# KONMAI_Cardreader.net
KiCad netlist of a schematic drawn in Altium Designer
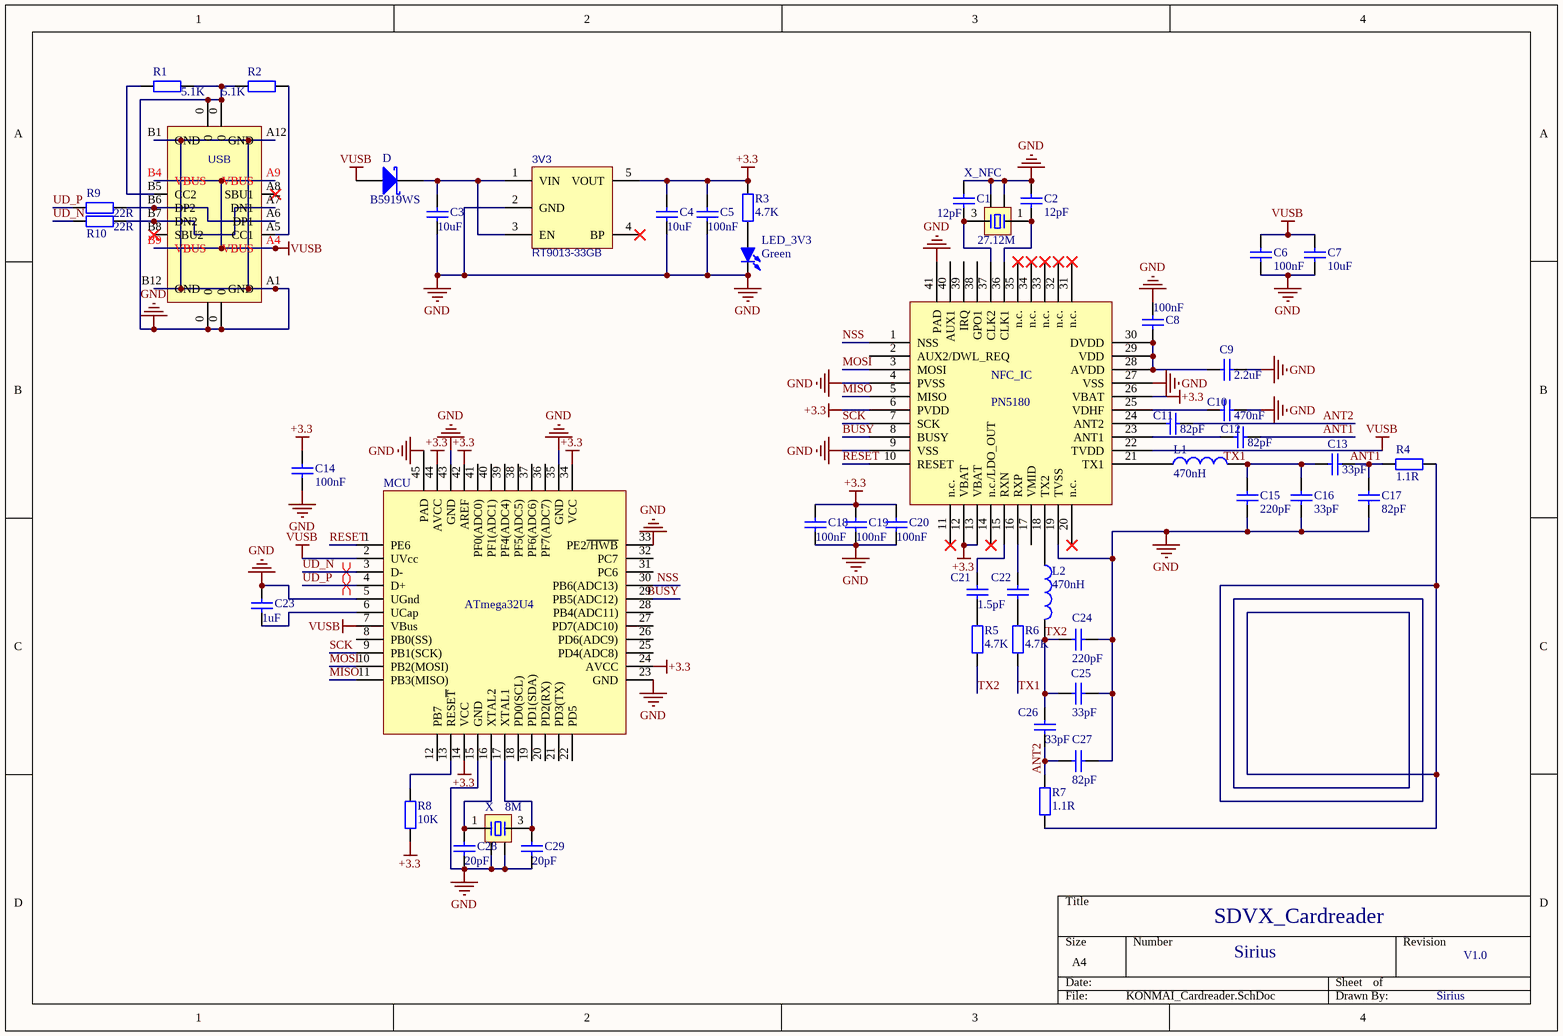
[diagram p0: KONMAI_Cardreader.SchDoc]

(export (version "E")
  (design (tool "Eeschema 10.0.6"))
  (components
    (comp (ref "3V3")
      (value "RT9013-33GB")
      (footprint "SOT-23-5")
      (description "LDO 3.0V/0.3A")
      (libsource (lib "0.7 - 电源类芯片") (part "RT9193-30GB"))
    )
    (comp (ref "C1")
      (value "12pF")
      (footprint "C0603_L")
      (description "贴片电容")
      (libsource (lib "0.1 - 电阻-电容-电感-电位器") (part "C"))
    )
    (comp (ref "C2")
      (value "12pF")
      (footprint "C0603_L")
      (description "贴片电容")
      (libsource (lib "0.1 - 电阻-电容-电感-电位器") (part "C"))
    )
    (comp (ref "C3")
      (value "10uF")
      (footprint "C0603_L")
      (description "贴片电容")
      (libsource (lib "0.1 - 电阻-电容-电感-电位器") (part "C"))
    )
    (comp (ref "C4")
      (value "10uF")
      (footprint "C0603_L")
      (description "贴片电容")
      (libsource (lib "0.1 - 电阻-电容-电感-电位器") (part "C"))
    )
    (comp (ref "C5")
      (value "100nF")
      (footprint "C0603_L")
      (description "贴片电容")
      (libsource (lib "0.1 - 电阻-电容-电感-电位器") (part "C"))
    )
    (comp (ref "C6")
      (value "100nF")
      (footprint "C0603_L")
      (description "TVDD续流电容")
      (libsource (lib "0.1 - 电阻-电容-电感-电位器") (part "C"))
    )
    (comp (ref "C7")
      (value "10uF")
      (footprint "C0603_L")
      (description "TVDD续流电容")
      (libsource (lib "0.1 - 电阻-电容-电感-电位器") (part "C"))
    )
    (comp (ref "C8")
      (value "100nF")
      (footprint "C0603_L")
      (description "DVDD滤波")
      (libsource (lib "0.1 - 电阻-电容-电感-电位器") (part "C"))
    )
    (comp (ref "C9")
      (value "2.2uF")
      (footprint "C0603_L")
      (description "AVDD滤波")
      (libsource (lib "0.1 - 电阻-电容-电感-电位器") (part "C"))
    )
    (comp (ref "C10")
      (value "470nF")
      (footprint "C0603_L")
      (description "贴片电容")
      (libsource (lib "0.1 - 电阻-电容-电感-电位器") (part "C"))
    )
    (comp (ref "C11")
      (value "82pF")
      (footprint "C0603_L")
      (description "贴片电容")
      (libsource (lib "0.1 - 电阻-电容-电感-电位器") (part "C"))
    )
    (comp (ref "C12")
      (value "82pF")
      (footprint "C0603_L")
      (description "贴片电容")
      (libsource (lib "0.1 - 电阻-电容-电感-电位器") (part "C"))
    )
    (comp (ref "C13")
      (value "33pF")
      (footprint "C0603_L")
      (description "贴片电容")
      (libsource (lib "0.1 - 电阻-电容-电感-电位器") (part "C"))
    )
    (comp (ref "C14")
      (value "100nF")
      (footprint "C0603_L")
      (description "AREF滤波电容")
      (libsource (lib "0.1 - 电阻-电容-电感-电位器") (part "C"))
    )
    (comp (ref "C15")
      (value "220pF")
      (footprint "C0603_L")
      (description "贴片电容")
      (libsource (lib "0.1 - 电阻-电容-电感-电位器") (part "C"))
    )
    (comp (ref "C16")
      (value "33pF")
      (footprint "C0603_L")
      (description "贴片电容")
      (libsource (lib "0.1 - 电阻-电容-电感-电位器") (part "C"))
    )
    (comp (ref "C17")
      (value "82pF")
      (footprint "C0603_L")
      (description "贴片电容")
      (libsource (lib "0.1 - 电阻-电容-电感-电位器") (part "C"))
    )
    (comp (ref "C18")
      (value "100nF")
      (footprint "C0603_L")
      (description "VBAT滤波")
      (libsource (lib "0.1 - 电阻-电容-电感-电位器") (part "C"))
    )
    (comp (ref "C19")
      (value "100nF")
      (footprint "C0603_L")
      (description "VBAT滤波")
      (libsource (lib "0.1 - 电阻-电容-电感-电位器") (part "C"))
    )
    (comp (ref "C20")
      (value "100nF")
      (footprint "C0603_L")
      (description "VBAT滤波")
      (libsource (lib "0.1 - 电阻-电容-电感-电位器") (part "C"))
    )
    (comp (ref "C21")
      (value "1.5pF")
      (footprint "C0603_L")
      (description "贴片电容")
      (libsource (lib "0.1 - 电阻-电容-电感-电位器") (part "C"))
    )
    (comp (ref "C22")
      (value "1.5pF")
      (footprint "C0603_L")
      (description "贴片电容")
      (libsource (lib "0.1 - 电阻-电容-电感-电位器") (part "C"))
    )
    (comp (ref "C23")
      (value "1uF")
      (footprint "C0603_L")
      (description "贴片电容")
      (libsource (lib "0.1 - 电阻-电容-电感-电位器") (part "C"))
    )
    (comp (ref "C24")
      (value "220pF")
      (footprint "C0603_L")
      (description "贴片电容")
      (libsource (lib "0.1 - 电阻-电容-电感-电位器") (part "C"))
    )
    (comp (ref "C25")
      (value "33pF")
      (footprint "C0603_L")
      (description "贴片电容")
      (libsource (lib "0.1 - 电阻-电容-电感-电位器") (part "C"))
    )
    (comp (ref "C26")
      (value "33pF")
      (footprint "C0603_L")
      (description "贴片电容")
      (libsource (lib "0.1 - 电阻-电容-电感-电位器") (part "C"))
    )
    (comp (ref "C27")
      (value "82pF")
      (footprint "C0603_L")
      (description "贴片电容")
      (libsource (lib "0.1 - 电阻-电容-电感-电位器") (part "C"))
    )
    (comp (ref "C28")
      (value "20pF")
      (footprint "C0603_L")
      (description "贴片电容")
      (libsource (lib "0.1 - 电阻-电容-电感-电位器") (part "C"))
    )
    (comp (ref "C29")
      (value "20pF")
      (footprint "C0603_L")
      (description "贴片电容")
      (libsource (lib "0.1 - 电阻-电容-电感-电位器") (part "C"))
    )
    (comp (ref "D")
      (value "B5919WS")
      (footprint "SOD-323")
      (description "肖特基二极管")
      (libsource (lib "0.2 - 二极管-TVS-ESD-整流桥") (part "1N5819"))
    )
    (comp (ref "L1")
      (value "470nH")
      (footprint "L0603")
      (description "贴片小功率电感")
      (libsource (lib "0.1 - 电阻-电容-电感-晶振-晶体-磁珠-电位器") (part "L"))
    )
    (comp (ref "L2")
      (value "470nH")
      (footprint "L0603")
      (description "贴片小功率电感")
      (libsource (lib "0.1 - 电阻-电容-电感-晶振-晶体-磁珠-电位器") (part "L"))
    )
    (comp (ref "LED_3V3")
      (value "Green")
      (footprint "LED0603_G")
      (description "贴片LED")
      (libsource (lib "0.3 - LED发光二极管") (part "LED-SMD"))
    )
    (comp (ref "MCU")
      (value "ATmega32U4")
      (footprint "44PW_ATM-M")
      (description "AVR单片机")
      (libsource (lib "Extra Sch") (part "ATmega32U4"))
    )
    (comp (ref "NFC_IC")
      (value "PN5180")
      (footprint "QFN40_PN5180_NXP-L")
      (description "NFC_IC")
      (libsource (lib "Extra Sch") (part "PN5180"))
    )
    (comp (ref "R1")
      (value "5.1K")
      (footprint "R0603_L")
      (description "贴片电阻")
      (libsource (lib "0.1 - 电阻-电容-电感-晶振-晶体-磁珠-电位器") (part "R"))
    )
    (comp (ref "R2")
      (value "5.1K")
      (footprint "R0603_L")
      (description "贴片电阻")
      (libsource (lib "0.1 - 电阻-电容-电感-晶振-晶体-磁珠-电位器") (part "R"))
    )
    (comp (ref "R3")
      (value "4.7K")
      (footprint "R0603_L")
      (description "贴片电阻")
      (libsource (lib "0.1 - 电阻-电容-电感-电位器") (part "R"))
    )
    (comp (ref "R4")
      (value "1.1R")
      (footprint "R0603_L")
      (description "贴片电阻")
      (libsource (lib "0.1 - 电阻-电容-电感-晶振-晶体-磁珠-电位器") (part "R"))
    )
    (comp (ref "R5")
      (value "4.7K")
      (footprint "R0603_L")
      (description "贴片电阻")
      (libsource (lib "0.1 - 电阻-电容-电感-晶振-晶体-磁珠-电位器") (part "R"))
    )
    (comp (ref "R6")
      (value "4.7K")
      (footprint "R0603_L")
      (description "贴片电阻")
      (libsource (lib "0.1 - 电阻-电容-电感-晶振-晶体-磁珠-电位器") (part "R"))
    )
    (comp (ref "R7")
      (value "1.1R")
      (footprint "R0603_L")
      (description "贴片电阻")
      (libsource (lib "0.1 - 电阻-电容-电感-晶振-晶体-磁珠-电位器") (part "R"))
    )
    (comp (ref "R8")
      (value "10K")
      (footprint "R0603_L")
      (description "贴片电阻")
      (libsource (lib "0.1 - 电阻-电容-电感-电位器") (part "R"))
    )
    (comp (ref "R9")
      (value "22R")
      (footprint "R0603_L")
      (description "贴片电阻")
      (libsource (lib "0.1 - 电阻-电容-电感-晶振-晶体-磁珠-电位器") (part "R"))
    )
    (comp (ref "R10")
      (value "22R")
      (footprint "R0603_L")
      (description "贴片电阻")
      (libsource (lib "0.1 - 电阻-电容-电感-晶振-晶体-磁珠-电位器") (part "R"))
    )
    (comp (ref "USB")
      (value "TYPE-C 2.0 -16P")
      (footprint "USB-C-SMD_16P")
      (description "USB2.0 Type-C 16Pin  母座")
      (libsource (lib "0.8 - 以太网-音频-Type-C USB插座") (part "USB2.0_Type-C_16Pin"))
    )
    (comp (ref "X")
      (value "8M")
      (footprint "XTAL-3225-4P")
      (description "4脚无源晶振(谐振器）")
      (libsource (lib "0.1 - 电阻-电容-电感-晶振-晶体-磁珠-电位器") (part "XTAL-4P"))
    )
    (comp (ref "X_NFC")
      (value "27.12M")
      (footprint "XTAL-3225-4P")
      (description "4脚无源晶振(谐振器）")
      (libsource (lib "") (part "XTAL-4P_1"))
    )
  )
  (nets
    (net (code "1") (name "+3.3") (class "Default")
      (node (ref "3V3") (pin "5") (pinfunction "VOUT_5") (pintype "passive"))
      (node (ref "C14") (pin "2") (pinfunction "2_2") (pintype "passive"))
      (node (ref "C18") (pin "2") (pinfunction "2_2") (pintype "passive"))
      (node (ref "C19") (pin "2") (pinfunction "2_2") (pintype "passive"))
      (node (ref "C20") (pin "2") (pinfunction "2_2") (pintype "passive"))
      (node (ref "C4") (pin "2") (pinfunction "2_2") (pintype "passive"))
      (node (ref "C5") (pin "2") (pinfunction "2_2") (pintype "passive"))
      (node (ref "MCU") (pin "14") (pinfunction "VCC_14") (pintype "passive"))
      (node (ref "MCU") (pin "24") (pinfunction "AVCC_24") (pintype "passive"))
      (node (ref "MCU") (pin "34") (pinfunction "VCC_34") (pintype "passive"))
      (node (ref "MCU") (pin "42") (pinfunction "AREF_42") (pintype "passive"))
      (node (ref "MCU") (pin "44") (pinfunction "AVCC_44") (pintype "passive"))
      (node (ref "NFC_IC") (pin "12") (pinfunction "VBAT_12") (pintype "passive"))
      (node (ref "NFC_IC") (pin "13") (pinfunction "VBAT_13") (pintype "passive"))
      (node (ref "NFC_IC") (pin "26") (pinfunction "VBAT_26") (pintype "passive"))
      (node (ref "NFC_IC") (pin "6") (pinfunction "PVDD_6") (pintype "passive"))
      (node (ref "R3") (pin "2") (pinfunction "2_2") (pintype "passive"))
      (node (ref "R8") (pin "1") (pinfunction "1_1") (pintype "passive"))
    )
    (net (code "2") (name "/ANT1") (class "Default")
      (node (ref "C12") (pin "1") (pinfunction "1_1") (pintype "passive"))
      (node (ref "C13") (pin "1") (pinfunction "1_1") (pintype "passive"))
      (node (ref "C17") (pin "2") (pinfunction "2_2") (pintype "passive"))
      (node (ref "R4") (pin "2") (pinfunction "2_2") (pintype "passive"))
    )
    (net (code "3") (name "/ANT2") (class "Default")
      (node (ref "C11") (pin "1") (pinfunction "1_1") (pintype "passive"))
      (node (ref "C26") (pin "2") (pinfunction "2_2") (pintype "passive"))
      (node (ref "C27") (pin "1") (pinfunction "1_1") (pintype "passive"))
      (node (ref "R7") (pin "1") (pinfunction "1_1") (pintype "passive"))
    )
    (net (code "4") (name "/BUSY") (class "Default")
      (node (ref "MCU") (pin "29") (pinfunction "PB5(ADC12)_29") (pintype "passive"))
      (node (ref "NFC_IC") (pin "8") (pinfunction "BUSY_8") (pintype "passive"))
    )
    (net (code "5") (name "/MISO") (class "Default")
      (node (ref "MCU") (pin "11") (pinfunction "PB3(MISO)_11") (pintype "passive"))
      (node (ref "NFC_IC") (pin "5") (pinfunction "MISO_5") (pintype "passive"))
    )
    (net (code "6") (name "/MOSI") (class "Default")
      (node (ref "MCU") (pin "10") (pinfunction "PB2(MOSI)_10") (pintype "passive"))
      (node (ref "NFC_IC") (pin "3") (pinfunction "MOSI_3") (pintype "passive"))
    )
    (net (code "7") (name "/NSS") (class "Default")
      (node (ref "MCU") (pin "30") (pinfunction "PB6(ADC13)_30") (pintype "passive"))
      (node (ref "NFC_IC") (pin "1") (pinfunction "NSS_1") (pintype "passive"))
    )
    (net (code "8") (name "/RESET") (class "Default")
      (node (ref "MCU") (pin "1") (pinfunction "PE6_1") (pintype "passive"))
      (node (ref "NFC_IC") (pin "10") (pinfunction "RESET_10") (pintype "passive"))
    )
    (net (code "9") (name "/SCK") (class "Default")
      (node (ref "MCU") (pin "9") (pinfunction "PB1(SCK)_9") (pintype "passive"))
      (node (ref "NFC_IC") (pin "7") (pinfunction "SCK_7") (pintype "passive"))
    )
    (net (code "10") (name "/TX1") (class "Default")
      (node (ref "C13") (pin "2") (pinfunction "2_2") (pintype "passive"))
      (node (ref "C15") (pin "2") (pinfunction "2_2") (pintype "passive"))
      (node (ref "C16") (pin "1") (pinfunction "1_1") (pintype "passive"))
      (node (ref "L1") (pin "2") (pinfunction "2_2") (pintype "passive"))
      (node (ref "R6") (pin "1") (pinfunction "1_1") (pintype "passive"))
    )
    (net (code "11") (name "/TX2") (class "Default")
      (node (ref "C24") (pin "2") (pinfunction "2_2") (pintype "passive"))
      (node (ref "C25") (pin "1") (pinfunction "1_1") (pintype "passive"))
      (node (ref "C26") (pin "1") (pinfunction "1_1") (pintype "passive"))
      (node (ref "L2") (pin "2") (pinfunction "2_2") (pintype "passive"))
      (node (ref "R5") (pin "1") (pinfunction "1_1") (pintype "passive"))
    )
    (net (code "12") (name "/UD_N") (class "Default")
      (node (ref "MCU") (pin "3") (pinfunction "D-_3") (pintype "passive"))
      (node (ref "R10") (pin "1") (pinfunction "1_1") (pintype "passive"))
    )
    (net (code "13") (name "/UD_P") (class "Default")
      (node (ref "MCU") (pin "4") (pinfunction "D+_4") (pintype "passive"))
      (node (ref "R9") (pin "1") (pinfunction "1_1") (pintype "passive"))
    )
    (net (code "14") (name "GND") (class "Default")
      (node (ref "3V3") (pin "2") (pinfunction "GND_2") (pintype "passive"))
      (node (ref "C1") (pin "1") (pinfunction "1_1") (pintype "passive"))
      (node (ref "C10") (pin "2") (pinfunction "2_2") (pintype "passive"))
      (node (ref "C14") (pin "1") (pinfunction "1_1") (pintype "passive"))
      (node (ref "C15") (pin "1") (pinfunction "1_1") (pintype "passive"))
      (node (ref "C16") (pin "2") (pinfunction "2_2") (pintype "passive"))
      (node (ref "C17") (pin "1") (pinfunction "1_1") (pintype "passive"))
      (node (ref "C18") (pin "1") (pinfunction "1_1") (pintype "passive"))
      (node (ref "C19") (pin "1") (pinfunction "1_1") (pintype "passive"))
      (node (ref "C2") (pin "1") (pinfunction "1_1") (pintype "passive"))
      (node (ref "C20") (pin "1") (pinfunction "1_1") (pintype "passive"))
      (node (ref "C23") (pin "1") (pinfunction "1_1") (pintype "passive"))
      (node (ref "C24") (pin "1") (pinfunction "1_1") (pintype "passive"))
      (node (ref "C25") (pin "2") (pinfunction "2_2") (pintype "passive"))
      (node (ref "C27") (pin "2") (pinfunction "2_2") (pintype "passive"))
      (node (ref "C28") (pin "1") (pinfunction "1_1") (pintype "passive"))
      (node (ref "C29") (pin "1") (pinfunction "1_1") (pintype "passive"))
      (node (ref "C3") (pin "1") (pinfunction "1_1") (pintype "passive"))
      (node (ref "C4") (pin "1") (pinfunction "1_1") (pintype "passive"))
      (node (ref "C5") (pin "1") (pinfunction "1_1") (pintype "passive"))
      (node (ref "C6") (pin "2") (pinfunction "2_2") (pintype "passive"))
      (node (ref "C7") (pin "2") (pinfunction "2_2") (pintype "passive"))
      (node (ref "C8") (pin "2") (pinfunction "2_2") (pintype "passive"))
      (node (ref "C9") (pin "1") (pinfunction "1_1") (pintype "passive"))
      (node (ref "LED_3V3") (pin "2") (pinfunction "K_2") (pintype "passive"))
      (node (ref "MCU") (pin "15") (pinfunction "GND_15") (pintype "passive"))
      (node (ref "MCU") (pin "23") (pinfunction "GND_23") (pintype "passive"))
      (node (ref "MCU") (pin "33") (pinfunction "PE2~{/HWB}_33") (pintype "passive"))
      (node (ref "MCU") (pin "35") (pinfunction "GND_35") (pintype "passive"))
      (node (ref "MCU") (pin "43") (pinfunction "GND_43") (pintype "passive"))
      (node (ref "MCU") (pin "45") (pinfunction "PAD_45") (pintype "passive"))
      (node (ref "MCU") (pin "5") (pinfunction "UGnd_5") (pintype "passive"))
      (node (ref "NFC_IC") (pin "19") (pinfunction "TVSS_19") (pintype "passive"))
      (node (ref "NFC_IC") (pin "27") (pinfunction "VSS_27") (pintype "passive"))
      (node (ref "NFC_IC") (pin "4") (pinfunction "PVSS_4") (pintype "passive"))
      (node (ref "NFC_IC") (pin "41") (pinfunction "PAD_41") (pintype "passive"))
      (node (ref "NFC_IC") (pin "9") (pinfunction "VSS_9") (pintype "passive"))
      (node (ref "R1") (pin "2") (pinfunction "2_2") (pintype "passive"))
      (node (ref "R2") (pin "1") (pinfunction "1_1") (pintype "passive"))
      (node (ref "USB") (pin "0") (pinfunction "0_0") (pintype "passive"))
      (node (ref "USB") (pin "A1") (pinfunction "GND_A1") (pintype "passive"))
      (node (ref "USB") (pin "A12") (pinfunction "GND_A12") (pintype "passive"))
      (node (ref "USB") (pin "B1") (pinfunction "GND_B1") (pintype "passive"))
      (node (ref "USB") (pin "B12") (pinfunction "GND_B12") (pintype "passive"))
      (node (ref "X") (pin "2") (pinfunction "2_2") (pintype "passive"))
      (node (ref "X") (pin "4") (pinfunction "4_4") (pintype "passive"))
      (node (ref "X_NFC") (pin "2") (pinfunction "2_2") (pintype "passive"))
      (node (ref "X_NFC") (pin "4") (pinfunction "4_4") (pintype "passive"))
    )
    (net (code "15") (name "Net-(3V3-EN)") (class "Default")
      (node (ref "3V3") (pin "1") (pinfunction "VIN_1") (pintype "passive"))
      (node (ref "3V3") (pin "3") (pinfunction "EN_3") (pintype "passive"))
      (node (ref "C3") (pin "2") (pinfunction "2_2") (pintype "passive"))
      (node (ref "D") (pin "2") (pinfunction "K_2") (pintype "passive"))
    )
    (net (code "16") (name "Net-(C21-Pad1)") (class "Default")
      (node (ref "C21") (pin "1") (pinfunction "1_1") (pintype "passive"))
      (node (ref "R5") (pin "2") (pinfunction "2_2") (pintype "passive"))
    )
    (net (code "17") (name "Net-(C22-Pad1)") (class "Default")
      (node (ref "C22") (pin "1") (pinfunction "1_1") (pintype "passive"))
      (node (ref "R6") (pin "2") (pinfunction "2_2") (pintype "passive"))
    )
    (net (code "18") (name "Net-(LED_3V3-A)") (class "Default")
      (node (ref "LED_3V3") (pin "1") (pinfunction "A_1") (pintype "passive"))
      (node (ref "R3") (pin "1") (pinfunction "1_1") (pintype "passive"))
    )
    (net (code "19") (name "Net-(MCU-RESE~{T})") (class "Default")
      (node (ref "MCU") (pin "13") (pinfunction "RESE~{T}_13") (pintype "passive"))
      (node (ref "R8") (pin "2") (pinfunction "2_2") (pintype "passive"))
    )
    (net (code "20") (name "Net-(MCU-UCap)") (class "Default")
      (node (ref "C23") (pin "2") (pinfunction "2_2") (pintype "passive"))
      (node (ref "MCU") (pin "6") (pinfunction "UCap_6") (pintype "passive"))
    )
    (net (code "21") (name "Net-(MCU-XTAL1)") (class "Default")
      (node (ref "C29") (pin "2") (pinfunction "2_2") (pintype "passive"))
      (node (ref "MCU") (pin "17") (pinfunction "XTAL1_17") (pintype "passive"))
      (node (ref "X") (pin "3") (pinfunction "3_3") (pintype "passive"))
    )
    (net (code "22") (name "Net-(MCU-XTAL2)") (class "Default")
      (node (ref "C28") (pin "2") (pinfunction "2_2") (pintype "passive"))
      (node (ref "MCU") (pin "16") (pinfunction "XTAL2_16") (pintype "passive"))
      (node (ref "X") (pin "1") (pinfunction "1_1") (pintype "passive"))
    )
    (net (code "23") (name "Net-(NFC_IC-ANT1)") (class "Default")
      (node (ref "C12") (pin "2") (pinfunction "2_2") (pintype "passive"))
      (node (ref "NFC_IC") (pin "23") (pinfunction "ANT1_23") (pintype "passive"))
    )
    (net (code "24") (name "Net-(NFC_IC-ANT2)") (class "Default")
      (node (ref "C11") (pin "2") (pinfunction "2_2") (pintype "passive"))
      (node (ref "NFC_IC") (pin "24") (pinfunction "ANT2_24") (pintype "passive"))
    )
    (net (code "25") (name "Net-(NFC_IC-AVDD)") (class "Default")
      (node (ref "C8") (pin "1") (pinfunction "1_1") (pintype "passive"))
      (node (ref "C9") (pin "2") (pinfunction "2_2") (pintype "passive"))
      (node (ref "NFC_IC") (pin "28") (pinfunction "AVDD_28") (pintype "passive"))
      (node (ref "NFC_IC") (pin "29") (pinfunction "VDD_29") (pintype "passive"))
      (node (ref "NFC_IC") (pin "30") (pinfunction "DVDD_30") (pintype "passive"))
    )
    (net (code "26") (name "Net-(NFC_IC-CLK1)") (class "Default")
      (node (ref "C2") (pin "2") (pinfunction "2_2") (pintype "passive"))
      (node (ref "NFC_IC") (pin "36") (pinfunction "CLK1_36") (pintype "passive"))
      (node (ref "X_NFC") (pin "1") (pinfunction "1_1") (pintype "passive"))
    )
    (net (code "27") (name "Net-(NFC_IC-CLK2)") (class "Default")
      (node (ref "C1") (pin "2") (pinfunction "2_2") (pintype "passive"))
      (node (ref "NFC_IC") (pin "37") (pinfunction "CLK2_37") (pintype "passive"))
      (node (ref "X_NFC") (pin "3") (pinfunction "3_3") (pintype "passive"))
    )
    (net (code "28") (name "Net-(NFC_IC-RXN)") (class "Default")
      (node (ref "C21") (pin "2") (pinfunction "2_2") (pintype "passive"))
      (node (ref "NFC_IC") (pin "15") (pinfunction "RXN_15") (pintype "passive"))
    )
    (net (code "29") (name "Net-(NFC_IC-RXP)") (class "Default")
      (node (ref "C22") (pin "2") (pinfunction "2_2") (pintype "passive"))
      (node (ref "NFC_IC") (pin "16") (pinfunction "RXP_16") (pintype "passive"))
    )
    (net (code "30") (name "Net-(NFC_IC-TX1)") (class "Default")
      (node (ref "L1") (pin "1") (pinfunction "1_1") (pintype "passive"))
      (node (ref "NFC_IC") (pin "21") (pinfunction "TX1_21") (pintype "passive"))
    )
    (net (code "31") (name "Net-(NFC_IC-TX2)") (class "Default")
      (node (ref "L2") (pin "1") (pinfunction "1_1") (pintype "passive"))
      (node (ref "NFC_IC") (pin "18") (pinfunction "TX2_18") (pintype "passive"))
    )
    (net (code "32") (name "Net-(NFC_IC-VDHF)") (class "Default")
      (node (ref "C10") (pin "1") (pinfunction "1_1") (pintype "passive"))
      (node (ref "NFC_IC") (pin "25") (pinfunction "VDHF_25") (pintype "passive"))
    )
    (net (code "33") (name "Net-(R4-Pad1)") (class "Default")
      (node (ref "R4") (pin "1") (pinfunction "1_1") (pintype "passive"))
      (node (ref "R7") (pin "2") (pinfunction "2_2") (pintype "passive"))
    )
    (net (code "34") (name "Net-(USB-CC1)") (class "Default")
      (node (ref "R2") (pin "2") (pinfunction "2_2") (pintype "passive"))
      (node (ref "USB") (pin "A5") (pinfunction "CC1_A5") (pintype "passive"))
    )
    (net (code "35") (name "Net-(USB-CC2)") (class "Default")
      (node (ref "R1") (pin "1") (pinfunction "1_1") (pintype "passive"))
      (node (ref "USB") (pin "B5") (pinfunction "CC2_B5") (pintype "passive"))
    )
    (net (code "36") (name "Net-(USB-DN1)") (class "Default")
      (node (ref "R10") (pin "2") (pinfunction "2_2") (pintype "passive"))
      (node (ref "USB") (pin "A7") (pinfunction "DN1_A7") (pintype "passive"))
      (node (ref "USB") (pin "B7") (pinfunction "DN2_B7") (pintype "passive"))
    )
    (net (code "37") (name "Net-(USB-DP1)") (class "Default")
      (node (ref "R9") (pin "2") (pinfunction "2_2") (pintype "passive"))
      (node (ref "USB") (pin "A6") (pinfunction "DP1_A6") (pintype "passive"))
      (node (ref "USB") (pin "B6") (pinfunction "DP2_B6") (pintype "passive"))
    )
    (net (code "38") (name "VUSB") (class "Default")
      (node (ref "C6") (pin "1") (pinfunction "1_1") (pintype "passive"))
      (node (ref "C7") (pin "1") (pinfunction "1_1") (pintype "passive"))
      (node (ref "D") (pin "1") (pinfunction "A_1") (pintype "passive"))
      (node (ref "MCU") (pin "2") (pinfunction "UVcc_2") (pintype "passive"))
      (node (ref "MCU") (pin "7") (pinfunction "VBus_7") (pintype "passive"))
      (node (ref "NFC_IC") (pin "22") (pinfunction "TVDD_22") (pintype "passive"))
      (node (ref "USB") (pin "A4") (pinfunction "VBUS_A4") (pintype "passive"))
      (node (ref "USB") (pin "A9") (pinfunction "VBUS_A9") (pintype "passive"))
      (node (ref "USB") (pin "B4") (pinfunction "VBUS_B4") (pintype "passive"))
      (node (ref "USB") (pin "B9") (pinfunction "VBUS_B9") (pintype "passive"))
    )
    (net (code "39") (name "unconnected-(3V3-BP-Pad4)") (class "Default")
      (node (ref "3V3") (pin "4") (pinfunction "BP_4") (pintype "passive+no_connect"))
    )
    (net (code "40") (name "unconnected-(MCU-PB0(SS)-Pad8)") (class "Default")
      (node (ref "MCU") (pin "8") (pinfunction "PB0(SS)_8") (pintype "passive"))
    )
    (net (code "41") (name "unconnected-(MCU-PB4(ADC11)-Pad28)") (class "Default")
      (node (ref "MCU") (pin "28") (pinfunction "PB4(ADC11)_28") (pintype "passive"))
    )
    (net (code "42") (name "unconnected-(MCU-PB7-Pad12)") (class "Default")
      (node (ref "MCU") (pin "12") (pinfunction "PB7_12") (pintype "passive"))
    )
    (net (code "43") (name "unconnected-(MCU-PC6-Pad31)") (class "Default")
      (node (ref "MCU") (pin "31") (pinfunction "PC6_31") (pintype "passive"))
    )
    (net (code "44") (name "unconnected-(MCU-PC7-Pad32)") (class "Default")
      (node (ref "MCU") (pin "32") (pinfunction "PC7_32") (pintype "passive"))
    )
    (net (code "45") (name "unconnected-(MCU-PD0(SCL)-Pad18)") (class "Default")
      (node (ref "MCU") (pin "18") (pinfunction "PD0(SCL)_18") (pintype "passive"))
    )
    (net (code "46") (name "unconnected-(MCU-PD1(SDA)-Pad19)") (class "Default")
      (node (ref "MCU") (pin "19") (pinfunction "PD1(SDA)_19") (pintype "passive"))
    )
    (net (code "47") (name "unconnected-(MCU-PD2(RX)-Pad20)") (class "Default")
      (node (ref "MCU") (pin "20") (pinfunction "PD2(RX)_20") (pintype "passive"))
    )
    (net (code "48") (name "unconnected-(MCU-PD3(TX)-Pad21)") (class "Default")
      (node (ref "MCU") (pin "21") (pinfunction "PD3(TX)_21") (pintype "passive"))
    )
    (net (code "49") (name "unconnected-(MCU-PD4(ADC8)-Pad25)") (class "Default")
      (node (ref "MCU") (pin "25") (pinfunction "PD4(ADC8)_25") (pintype "passive"))
    )
    (net (code "50") (name "unconnected-(MCU-PD5-Pad22)") (class "Default")
      (node (ref "MCU") (pin "22") (pinfunction "PD5_22") (pintype "passive"))
    )
    (net (code "51") (name "unconnected-(MCU-PD6(ADC9)-Pad26)") (class "Default")
      (node (ref "MCU") (pin "26") (pinfunction "PD6(ADC9)_26") (pintype "passive"))
    )
    (net (code "52") (name "unconnected-(MCU-PD7(ADC10)-Pad27)") (class "Default")
      (node (ref "MCU") (pin "27") (pinfunction "PD7(ADC10)_27") (pintype "passive"))
    )
    (net (code "53") (name "unconnected-(MCU-PF0(ADC0)-Pad41)") (class "Default")
      (node (ref "MCU") (pin "41") (pinfunction "PF0(ADC0)_41") (pintype "passive"))
    )
    (net (code "54") (name "unconnected-(MCU-PF1(ADC1)-Pad40)") (class "Default")
      (node (ref "MCU") (pin "40") (pinfunction "PF1(ADC1)_40") (pintype "passive"))
    )
    (net (code "55") (name "unconnected-(MCU-PF4(ADC4)-Pad39)") (class "Default")
      (node (ref "MCU") (pin "39") (pinfunction "PF4(ADC4)_39") (pintype "passive"))
    )
    (net (code "56") (name "unconnected-(MCU-PF5(ADC5)-Pad38)") (class "Default")
      (node (ref "MCU") (pin "38") (pinfunction "PF5(ADC5)_38") (pintype "passive"))
    )
    (net (code "57") (name "unconnected-(MCU-PF6(ADC6)-Pad37)") (class "Default")
      (node (ref "MCU") (pin "37") (pinfunction "PF6(ADC6)_37") (pintype "passive"))
    )
    (net (code "58") (name "unconnected-(MCU-PF7(ADC7)-Pad36)") (class "Default")
      (node (ref "MCU") (pin "36") (pinfunction "PF7(ADC7)_36") (pintype "passive"))
    )
    (net (code "59") (name "unconnected-(NFC_IC-AUX1-Pad40)") (class "Default")
      (node (ref "NFC_IC") (pin "40") (pinfunction "AUX1_40") (pintype "passive"))
    )
    (net (code "60") (name "unconnected-(NFC_IC-AUX2{slash}DWL_REQ-Pad2)") (class "Default")
      (node (ref "NFC_IC") (pin "2") (pinfunction "AUX2/DWL_REQ_2") (pintype "passive"))
    )
    (net (code "61") (name "unconnected-(NFC_IC-GPO1-Pad38)") (class "Default")
      (node (ref "NFC_IC") (pin "38") (pinfunction "GPO1_38") (pintype "passive"))
    )
    (net (code "62") (name "unconnected-(NFC_IC-IRQ-Pad39)") (class "Default")
      (node (ref "NFC_IC") (pin "39") (pinfunction "IRQ_39") (pintype "passive"))
    )
    (net (code "63") (name "unconnected-(NFC_IC-VMID-Pad17)") (class "Default")
      (node (ref "NFC_IC") (pin "17") (pinfunction "VMID_17") (pintype "passive"))
    )
    (net (code "64") (name "unconnected-(NFC_IC-n.c.-Pad11)") (class "Default")
      (node (ref "NFC_IC") (pin "11") (pinfunction "n.c._11") (pintype "passive+no_connect"))
    )
    (net (code "65") (name "unconnected-(NFC_IC-n.c.-Pad20)") (class "Default")
      (node (ref "NFC_IC") (pin "20") (pinfunction "n.c._20") (pintype "passive+no_connect"))
    )
    (net (code "66") (name "unconnected-(NFC_IC-n.c.-Pad31)") (class "Default")
      (node (ref "NFC_IC") (pin "31") (pinfunction "n.c._31") (pintype "passive+no_connect"))
    )
    (net (code "67") (name "unconnected-(NFC_IC-n.c.-Pad32)") (class "Default")
      (node (ref "NFC_IC") (pin "32") (pinfunction "n.c._32") (pintype "passive+no_connect"))
    )
    (net (code "68") (name "unconnected-(NFC_IC-n.c.-Pad33)") (class "Default")
      (node (ref "NFC_IC") (pin "33") (pinfunction "n.c._33") (pintype "passive+no_connect"))
    )
    (net (code "69") (name "unconnected-(NFC_IC-n.c.-Pad34)") (class "Default")
      (node (ref "NFC_IC") (pin "34") (pinfunction "n.c._34") (pintype "passive+no_connect"))
    )
    (net (code "70") (name "unconnected-(NFC_IC-n.c.-Pad35)") (class "Default")
      (node (ref "NFC_IC") (pin "35") (pinfunction "n.c._35") (pintype "passive+no_connect"))
    )
    (net (code "71") (name "unconnected-(NFC_IC-n.c.{slash}LDO_OUT-Pad14)") (class "Default")
      (node (ref "NFC_IC") (pin "14") (pinfunction "n.c./LDO_OUT_14") (pintype "passive+no_connect"))
    )
    (net (code "72") (name "unconnected-(USB-SBU1-PadA8)") (class "Default")
      (node (ref "USB") (pin "A8") (pinfunction "SBU1_A8") (pintype "passive+no_connect"))
    )
    (net (code "73") (name "unconnected-(USB-SBU2-PadB8)") (class "Default")
      (node (ref "USB") (pin "B8") (pinfunction "SBU2_B8") (pintype "passive+no_connect"))
    )
  )
)
